# taptdoa_1_x.net
KiCad netlist of a schematic drawn in EAGLE
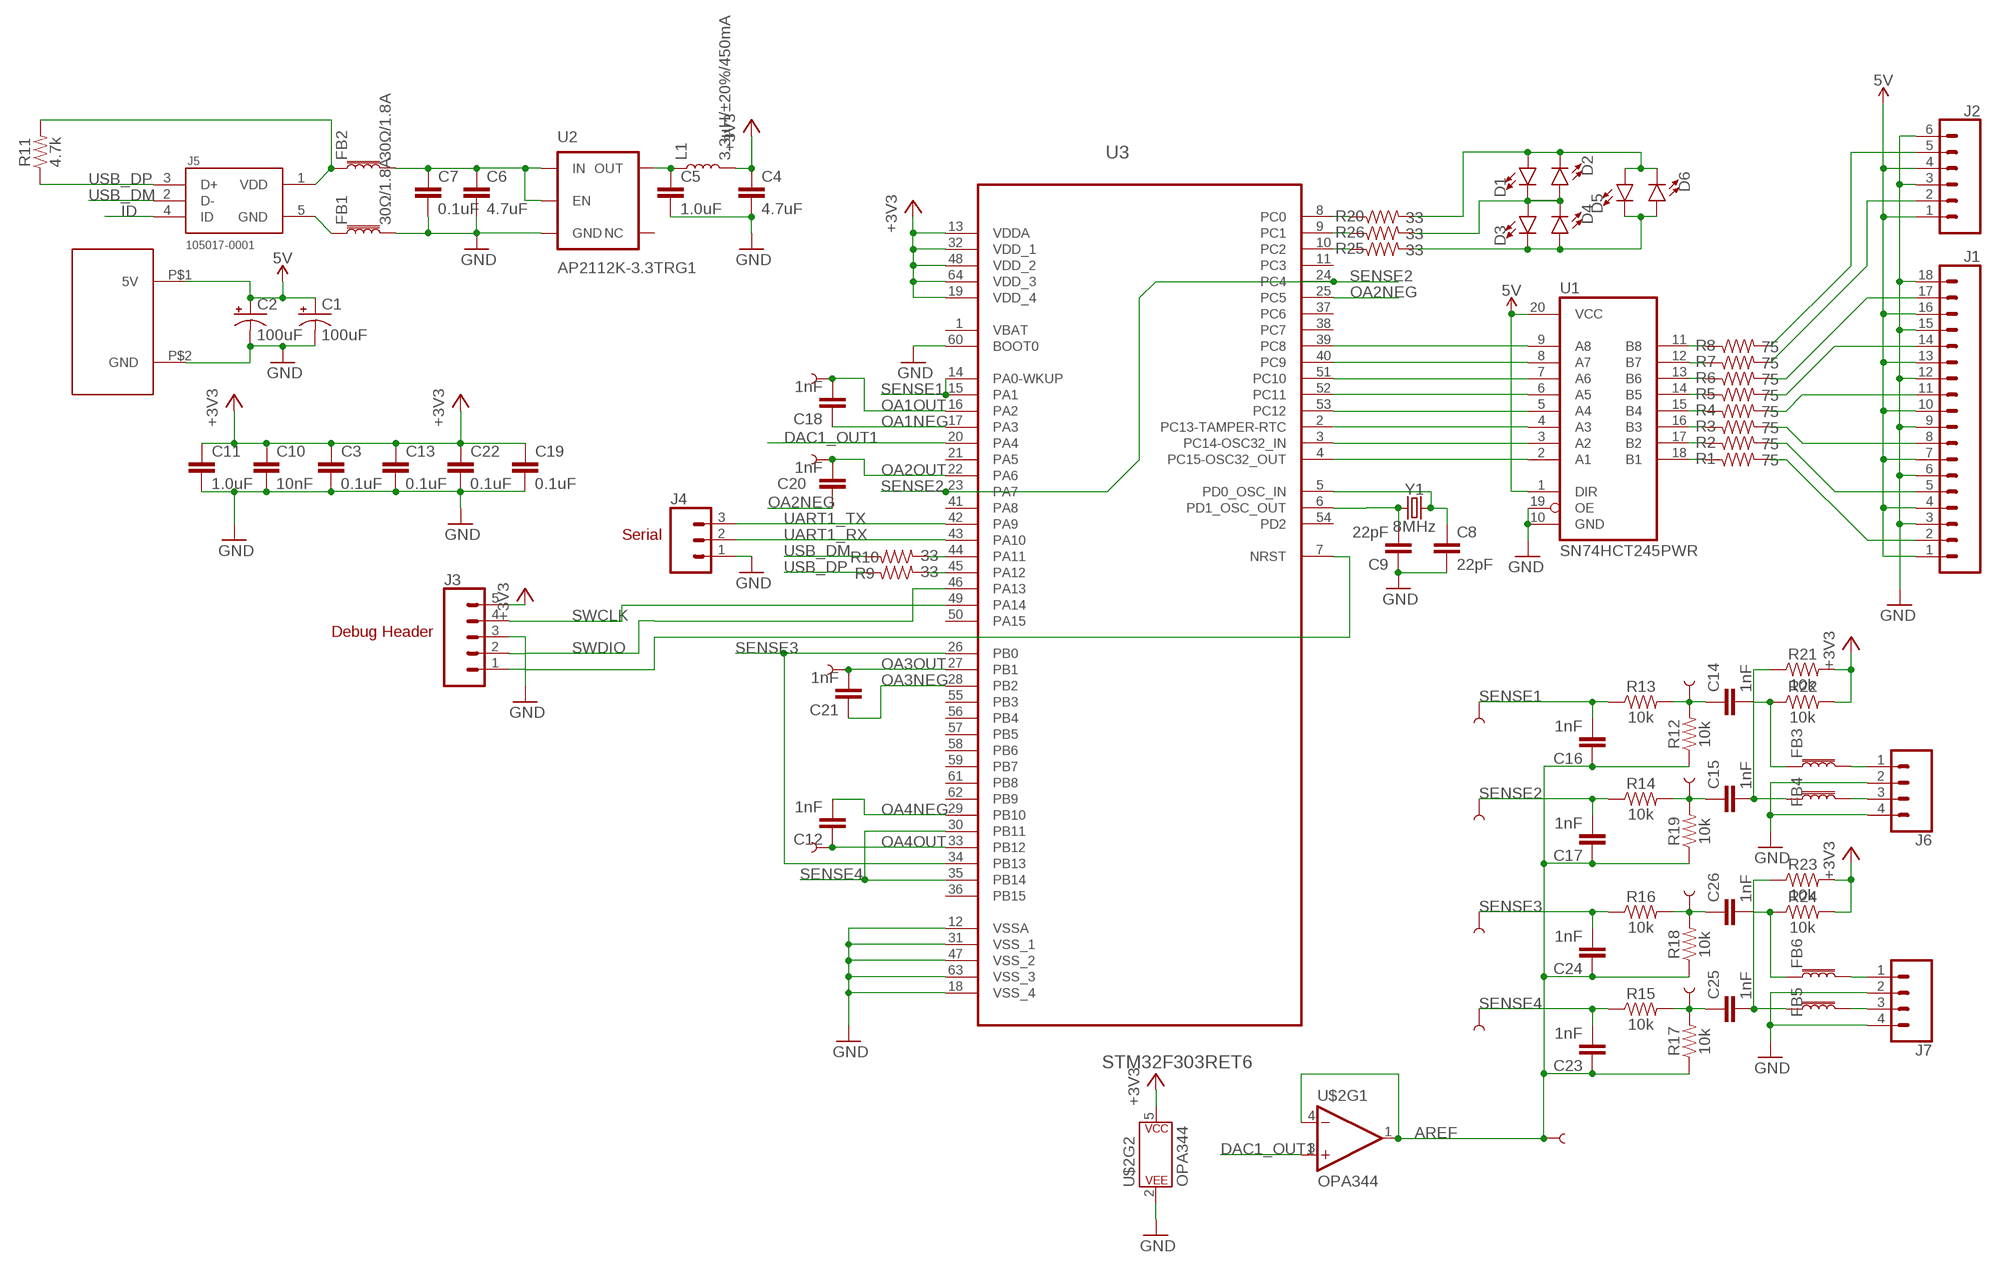
[diagram p0: schematic, sheet 1]

(export (version "E")
  (design (tool "Eeschema 10.0.6"))
  (components
    (comp (ref "C1")
      (value "100uF")
      (footprint "eagle-import:PANASONIC_D")
      (libsource (lib "eagle-import") (part "100UF-POLAR-25V-20%(ELEC)"))
    )
    (comp (ref "C2")
      (value "100uF")
      (footprint "eagle-import:PANASONIC_D")
      (libsource (lib "eagle-import") (part "100UF-POLAR-25V-20%(ELEC)"))
    )
    (comp (ref "C3")
      (value "0.1uF")
      (footprint "eagle-import:0603")
      (libsource (lib "eagle-import") (part "0.1UF-0603-25V-5%"))
    )
    (comp (ref "C4")
      (value "4.7uF")
      (footprint "eagle-import:0603")
      (libsource (lib "eagle-import") (part "4.7UF0603"))
    )
    (comp (ref "C5")
      (value "1.0uF")
      (footprint "eagle-import:0603")
      (libsource (lib "eagle-import") (part "1.0UF-0603-16V-10%"))
    )
    (comp (ref "C6")
      (value "4.7uF")
      (footprint "eagle-import:0603")
      (libsource (lib "eagle-import") (part "1.0UF-0603-16V-10%"))
    )
    (comp (ref "C7")
      (value "0.1uF")
      (footprint "eagle-import:0603")
      (libsource (lib "eagle-import") (part "0.1UF-0603-25V-5%"))
    )
    (comp (ref "C8")
      (value "22pF")
      (footprint "eagle-import:0603")
      (libsource (lib "eagle-import") (part "22PF-0603-50V-5%"))
    )
    (comp (ref "C9")
      (value "22pF")
      (footprint "eagle-import:0603")
      (libsource (lib "eagle-import") (part "22PF-0603-50V-5%"))
    )
    (comp (ref "C10")
      (value "10nF")
      (footprint "eagle-import:0603")
      (libsource (lib "eagle-import") (part "10NF-0603-50V-10%"))
    )
    (comp (ref "C11")
      (value "1.0uF")
      (footprint "eagle-import:0603")
      (libsource (lib "eagle-import") (part "1.0UF-0603-16V-10%"))
    )
    (comp (ref "C12")
      (value "1nF")
      (footprint "eagle-import:0603")
      (libsource (lib "eagle-import") (part "1.0UF-0603-16V-10%"))
    )
    (comp (ref "C13")
      (value "0.1uF")
      (footprint "eagle-import:0603")
      (libsource (lib "eagle-import") (part "0.1UF-0603-25V-5%"))
    )
    (comp (ref "C14")
      (value "1nF")
      (footprint "eagle-import:0603")
      (libsource (lib "eagle-import") (part "1.0UF-0603-16V-10%"))
    )
    (comp (ref "C15")
      (value "1nF")
      (footprint "eagle-import:0603")
      (libsource (lib "eagle-import") (part "1.0UF-0603-16V-10%"))
    )
    (comp (ref "C16")
      (value "1nF")
      (footprint "eagle-import:0603")
      (libsource (lib "eagle-import") (part "1.0UF-0603-16V-10%"))
    )
    (comp (ref "C17")
      (value "1nF")
      (footprint "eagle-import:0603")
      (libsource (lib "eagle-import") (part "1.0UF-0603-16V-10%"))
    )
    (comp (ref "C18")
      (value "1nF")
      (footprint "eagle-import:0603")
      (libsource (lib "eagle-import") (part "1.0UF-0603-16V-10%"))
    )
    (comp (ref "C19")
      (value "0.1uF")
      (footprint "eagle-import:0603")
      (libsource (lib "eagle-import") (part "0.1UF-0603-25V-5%"))
    )
    (comp (ref "C20")
      (value "1nF")
      (footprint "eagle-import:0603")
      (libsource (lib "eagle-import") (part "1.0UF-0603-16V-10%"))
    )
    (comp (ref "C21")
      (value "1nF")
      (footprint "eagle-import:0603")
      (libsource (lib "eagle-import") (part "1.0UF-0603-16V-10%"))
    )
    (comp (ref "C22")
      (value "0.1uF")
      (footprint "eagle-import:0603")
      (libsource (lib "eagle-import") (part "0.1UF-0603-25V-5%"))
    )
    (comp (ref "C23")
      (value "1nF")
      (footprint "eagle-import:0603")
      (libsource (lib "eagle-import") (part "1.0UF-0603-16V-10%"))
    )
    (comp (ref "C24")
      (value "1nF")
      (footprint "eagle-import:0603")
      (libsource (lib "eagle-import") (part "1.0UF-0603-16V-10%"))
    )
    (comp (ref "C25")
      (value "1nF")
      (footprint "eagle-import:0603")
      (libsource (lib "eagle-import") (part "1.0UF-0603-16V-10%"))
    )
    (comp (ref "C26")
      (value "1nF")
      (footprint "eagle-import:0603")
      (libsource (lib "eagle-import") (part "1.0UF-0603-16V-10%"))
    )
    (comp (ref "D1")
      (value "LED0603")
      (footprint "eagle-import:LED-0603")
      (libsource (lib "eagle-import") (part "LED0603"))
    )
    (comp (ref "D2")
      (value "LED0603")
      (footprint "eagle-import:LED-0603")
      (libsource (lib "eagle-import") (part "LED0603"))
    )
    (comp (ref "D3")
      (value "LED0603")
      (footprint "eagle-import:LED-0603")
      (libsource (lib "eagle-import") (part "LED0603"))
    )
    (comp (ref "D4")
      (value "LED0603")
      (footprint "eagle-import:LED-0603")
      (libsource (lib "eagle-import") (part "LED0603"))
    )
    (comp (ref "D5")
      (value "LED0603")
      (footprint "eagle-import:LED-0603")
      (libsource (lib "eagle-import") (part "LED0603"))
    )
    (comp (ref "D6")
      (value "LED0603")
      (footprint "eagle-import:LED-0603")
      (libsource (lib "eagle-import") (part "LED0603"))
    )
    (comp (ref "FB1")
      (value "30Ω/1.8A")
      (footprint "eagle-import:0603")
      (libsource (lib "eagle-import") (part "FERRITE_BEAD-0603"))
    )
    (comp (ref "FB2")
      (value "30Ω/1.8A")
      (footprint "eagle-import:0603")
      (libsource (lib "eagle-import") (part "FERRITE_BEAD-0603"))
    )
    (comp (ref "FB3")
      (value "30Ω/1.8A")
      (footprint "eagle-import:0603")
      (libsource (lib "eagle-import") (part "FERRITE_BEAD-0603"))
    )
    (comp (ref "FB4")
      (value "30Ω/1.8A")
      (footprint "eagle-import:0603")
      (libsource (lib "eagle-import") (part "FERRITE_BEAD-0603"))
    )
    (comp (ref "FB5")
      (value "30Ω/1.8A")
      (footprint "eagle-import:0603")
      (libsource (lib "eagle-import") (part "FERRITE_BEAD-0603"))
    )
    (comp (ref "FB6")
      (value "30Ω/1.8A")
      (footprint "eagle-import:0603")
      (libsource (lib "eagle-import") (part "FERRITE_BEAD-0603"))
    )
    (comp (ref "J1")
      (value "CONN_18")
      (footprint "eagle-import:1X18")
      (libsource (lib "eagle-import") (part "CONN_18"))
    )
    (comp (ref "J2")
      (value "CONN_06LOCK")
      (footprint "eagle-import:1X06_LOCK")
      (libsource (lib "eagle-import") (part "CONN_06LOCK"))
    )
    (comp (ref "J3")
      (value "CONN_05LOCK")
      (footprint "eagle-import:1X05_LOCK")
      (libsource (lib "eagle-import") (part "CONN_05LOCK"))
    )
    (comp (ref "J4")
      (value "CONN_03")
      (footprint "eagle-import:1X03")
      (libsource (lib "eagle-import") (part "CONN_03"))
    )
    (comp (ref "J5")
      (value "105017-0001")
      (footprint "eagle-import:MOLEX_105017-0001")
      (fields (field (name "MF") "Molex"))
      (libsource (lib "eagle-import") (part "105017-0001"))
    )
    (comp (ref "J6")
      (value "CONN_04LOCK_LONGPADS")
      (footprint "eagle-import:1X04_LOCK_LONGPADS")
      (libsource (lib "eagle-import") (part "CONN_04LOCK_LONGPADS"))
    )
    (comp (ref "J7")
      (value "CONN_04LOCK_LONGPADS")
      (footprint "eagle-import:1X04_LOCK_LONGPADS")
      (libsource (lib "eagle-import") (part "CONN_04LOCK_LONGPADS"))
    )
    (comp (ref "L1")
      (value "3.3µH/±20%/450mA")
      (footprint "eagle-import:0805")
      (libsource (lib "eagle-import") (part "INDUCTOR-0805-3.3UH"))
    )
    (comp (ref "R1")
      (value "75")
      (footprint "eagle-import:0603")
      (libsource (lib "eagle-import") (part "100OHM-0603-1/4W-5%"))
    )
    (comp (ref "R2")
      (value "75")
      (footprint "eagle-import:0603")
      (libsource (lib "eagle-import") (part "100OHM-0603-1/4W-5%"))
    )
    (comp (ref "R3")
      (value "75")
      (footprint "eagle-import:0603")
      (libsource (lib "eagle-import") (part "100OHM-0603-1/4W-5%"))
    )
    (comp (ref "R4")
      (value "75")
      (footprint "eagle-import:0603")
      (libsource (lib "eagle-import") (part "100OHM-0603-1/4W-5%"))
    )
    (comp (ref "R5")
      (value "75")
      (footprint "eagle-import:0603")
      (libsource (lib "eagle-import") (part "100OHM-0603-1/4W-5%"))
    )
    (comp (ref "R6")
      (value "75")
      (footprint "eagle-import:0603")
      (libsource (lib "eagle-import") (part "100OHM-0603-1/4W-5%"))
    )
    (comp (ref "R7")
      (value "75")
      (footprint "eagle-import:0603")
      (libsource (lib "eagle-import") (part "100OHM-0603-1/4W-5%"))
    )
    (comp (ref "R8")
      (value "75")
      (footprint "eagle-import:0603")
      (libsource (lib "eagle-import") (part "100OHM-0603-1/4W-5%"))
    )
    (comp (ref "R9")
      (value "33")
      (footprint "eagle-import:0603")
      (libsource (lib "eagle-import") (part "100OHM-0603-1/4W-5%"))
    )
    (comp (ref "R10")
      (value "33")
      (footprint "eagle-import:0603")
      (libsource (lib "eagle-import") (part "100OHM-0603-1/4W-5%"))
    )
    (comp (ref "R11")
      (value "4.7k")
      (footprint "eagle-import:0603")
      (libsource (lib "eagle-import") (part "RESISTOR0603"))
    )
    (comp (ref "R12")
      (value "10k")
      (footprint "eagle-import:0603")
      (libsource (lib "eagle-import") (part "RESISTOR0603"))
    )
    (comp (ref "R13")
      (value "10k")
      (footprint "eagle-import:0603")
      (libsource (lib "eagle-import") (part "RESISTOR0603"))
    )
    (comp (ref "R14")
      (value "10k")
      (footprint "eagle-import:0603")
      (libsource (lib "eagle-import") (part "RESISTOR0603"))
    )
    (comp (ref "R15")
      (value "10k")
      (footprint "eagle-import:0603")
      (libsource (lib "eagle-import") (part "RESISTOR0603"))
    )
    (comp (ref "R16")
      (value "10k")
      (footprint "eagle-import:0603")
      (libsource (lib "eagle-import") (part "RESISTOR0603"))
    )
    (comp (ref "R17")
      (value "10k")
      (footprint "eagle-import:0603")
      (libsource (lib "eagle-import") (part "RESISTOR0603"))
    )
    (comp (ref "R18")
      (value "10k")
      (footprint "eagle-import:0603")
      (libsource (lib "eagle-import") (part "RESISTOR0603"))
    )
    (comp (ref "R19")
      (value "10k")
      (footprint "eagle-import:0603")
      (libsource (lib "eagle-import") (part "RESISTOR0603"))
    )
    (comp (ref "R20")
      (value "33")
      (footprint "eagle-import:0603")
      (libsource (lib "eagle-import") (part "100OHM-0603-1/4W-5%"))
    )
    (comp (ref "R21")
      (value "10k")
      (footprint "eagle-import:0603")
      (libsource (lib "eagle-import") (part "RESISTOR0603"))
    )
    (comp (ref "R22")
      (value "10k")
      (footprint "eagle-import:0603")
      (libsource (lib "eagle-import") (part "RESISTOR0603"))
    )
    (comp (ref "R23")
      (value "10k")
      (footprint "eagle-import:0603")
      (libsource (lib "eagle-import") (part "RESISTOR0603"))
    )
    (comp (ref "R24")
      (value "10k")
      (footprint "eagle-import:0603")
      (libsource (lib "eagle-import") (part "RESISTOR0603"))
    )
    (comp (ref "R25")
      (value "33")
      (footprint "eagle-import:0603")
      (libsource (lib "eagle-import") (part "100OHM-0603-1/4W-5%"))
    )
    (comp (ref "R26")
      (value "33")
      (footprint "eagle-import:0603")
      (libsource (lib "eagle-import") (part "100OHM-0603-1/4W-5%"))
    )
    (comp (ref "TP1")
      (value "TEST-POINT3X4")
      (footprint "eagle-import:PAD.03X.04")
      (libsource (lib "eagle-import") (part "TEST-POINT3X4"))
    )
    (comp (ref "TP2")
      (value "TEST-POINT3X4")
      (footprint "eagle-import:PAD.03X.04")
      (libsource (lib "eagle-import") (part "TEST-POINT3X4"))
    )
    (comp (ref "TP3")
      (value "TEST-POINT3X4")
      (footprint "eagle-import:PAD.03X.04")
      (libsource (lib "eagle-import") (part "TEST-POINT3X4"))
    )
    (comp (ref "TP4")
      (value "TEST-POINT3X4")
      (footprint "eagle-import:PAD.03X.04")
      (libsource (lib "eagle-import") (part "TEST-POINT3X4"))
    )
    (comp (ref "TP5")
      (value "TEST-POINT3X4")
      (footprint "eagle-import:PAD.03X.04")
      (libsource (lib "eagle-import") (part "TEST-POINT3X4"))
    )
    (comp (ref "TP6")
      (value "TEST-POINT3X4")
      (footprint "eagle-import:PAD.03X.04")
      (libsource (lib "eagle-import") (part "TEST-POINT3X4"))
    )
    (comp (ref "TP7")
      (value "TEST-POINT3X4")
      (footprint "eagle-import:PAD.03X.04")
      (libsource (lib "eagle-import") (part "TEST-POINT3X4"))
    )
    (comp (ref "TP8")
      (value "TEST-POINT3X4")
      (footprint "eagle-import:PAD.03X.04")
      (libsource (lib "eagle-import") (part "TEST-POINT3X4"))
    )
    (comp (ref "TP9")
      (value "TEST-POINT3X4")
      (footprint "eagle-import:PAD.03X.04")
      (libsource (lib "eagle-import") (part "TEST-POINT3X4"))
    )
    (comp (ref "TP10")
      (value "TEST-POINT3X4")
      (footprint "eagle-import:PAD.03X.04")
      (libsource (lib "eagle-import") (part "TEST-POINT3X4"))
    )
    (comp (ref "TP11")
      (value "TEST-POINT3X4")
      (footprint "eagle-import:PAD.03X.04")
      (libsource (lib "eagle-import") (part "TEST-POINT3X4"))
    )
    (comp (ref "TP12")
      (value "TEST-POINT3X4")
      (footprint "eagle-import:PAD.03X.04")
      (libsource (lib "eagle-import") (part "TEST-POINT3X4"))
    )
    (comp (ref "TP13")
      (value "TEST-POINT3X4")
      (footprint "eagle-import:PAD.03X.04")
      (libsource (lib "eagle-import") (part "TEST-POINT3X4"))
    )
    (comp (ref "U$1")
      (value "XT30XT30_THRUHOLE")
      (footprint "eagle-import:ZT30")
      (libsource (lib "eagle-import") (part "XT30XT30_THRUHOLE"))
    )
    (comp (ref "U$2")
      (value "OPA344")
      (footprint "eagle-import:SOT23-5")
      (libsource (lib "eagle-import") (part "OPA344"))
    )
    (comp (ref "U1")
      (value "SN74HCT245PWR")
      (footprint "eagle-import:TSSOP20")
      (libsource (lib "eagle-import") (part "74245PW"))
    )
    (comp (ref "U2")
      (value "AP2112K-3.3TRG1")
      (footprint "eagle-import:SOT23-5")
      (libsource (lib "eagle-import") (part "V_REG_AP2112K-3.3V"))
    )
    (comp (ref "U3")
      (value "STM32F303RET6")
      (footprint "eagle-import:QFP50P1200X1200X160-64N")
      (fields (field (name "MPN") "STM32F103RBT6"))
      (libsource (lib "eagle-import") (part "STM32F103RBT6"))
    )
    (comp (ref "Y1")
      (value "8MHz")
      (footprint "eagle-import:HC49UP")
      (libsource (lib "eagle-import") (part "CRYSTALSMD-HC49UP"))
    )
  )
  (nets
    (net (code "1") (name "+3V3") (class "Default")
      (node (ref "C10") (pin "1") (pinfunction "1_1") (pintype "passive"))
      (node (ref "C11") (pin "1") (pinfunction "1_1") (pintype "passive"))
      (node (ref "C13") (pin "1") (pinfunction "1_1") (pintype "passive"))
      (node (ref "C19") (pin "1") (pinfunction "1_1") (pintype "passive"))
      (node (ref "C22") (pin "1") (pinfunction "1_1") (pintype "passive"))
      (node (ref "C3") (pin "1") (pinfunction "1_1") (pintype "passive"))
      (node (ref "C4") (pin "1") (pinfunction "1_1") (pintype "passive"))
      (node (ref "J3") (pin "5") (pinfunction "5_5") (pintype "passive"))
      (node (ref "L1") (pin "2") (pinfunction "2_2") (pintype "passive"))
      (node (ref "R21") (pin "2") (pinfunction "2_2") (pintype "passive"))
      (node (ref "R22") (pin "2") (pinfunction "2_2") (pintype "passive"))
      (node (ref "R23") (pin "2") (pinfunction "2_2") (pintype "passive"))
      (node (ref "R24") (pin "2") (pinfunction "2_2") (pintype "passive"))
      (node (ref "U$2") (pin "5") (pinfunction "P$V+_5") (pintype "bidirectional"))
      (node (ref "U3") (pin "13") (pinfunction "VDDA_13") (pintype "power_in"))
      (node (ref "U3") (pin "19") (pinfunction "VDD_4_19") (pintype "power_in"))
      (node (ref "U3") (pin "32") (pinfunction "VDD_1_32") (pintype "power_in"))
      (node (ref "U3") (pin "48") (pinfunction "VDD_2_48") (pintype "power_in"))
      (node (ref "U3") (pin "64") (pinfunction "VDD_3_64") (pintype "power_in"))
    )
    (net (code "2") (name "/AREF") (class "Default")
      (node (ref "C16") (pin "1") (pinfunction "1_1") (pintype "passive"))
      (node (ref "C17") (pin "1") (pinfunction "1_1") (pintype "passive"))
      (node (ref "C23") (pin "1") (pinfunction "1_1") (pintype "passive"))
      (node (ref "C24") (pin "1") (pinfunction "1_1") (pintype "passive"))
      (node (ref "R12") (pin "1") (pinfunction "1_1") (pintype "passive"))
      (node (ref "R17") (pin "1") (pinfunction "1_1") (pintype "passive"))
      (node (ref "R18") (pin "1") (pinfunction "1_1") (pintype "passive"))
      (node (ref "R19") (pin "1") (pinfunction "1_1") (pintype "passive"))
      (node (ref "TP8") (pin "P$1") (pinfunction "1_P$1") (pintype "bidirectional"))
      (node (ref "U$2") (pin "1") (pinfunction "OUT_1") (pintype "output"))
      (node (ref "U$2") (pin "4") (pinfunction "-IN_4") (pintype "input"))
    )
    (net (code "3") (name "/DAC1_OUT1") (class "Default")
      (node (ref "U$2") (pin "3") (pinfunction "+IN_3") (pintype "input"))
      (node (ref "U3") (pin "20") (pinfunction "PA4_20") (pintype "bidirectional"))
    )
    (net (code "4") (name "/ID") (class "Default")
      (node (ref "J5") (pin "4") (pinfunction "ID_4") (pintype "passive"))
    )
    (net (code "5") (name "/OA1NEG") (class "Default")
      (node (ref "C18") (pin "1") (pinfunction "1_1") (pintype "passive"))
      (node (ref "U3") (pin "17") (pinfunction "PA3_17") (pintype "bidirectional"))
    )
    (net (code "6") (name "/OA1OUT") (class "Default")
      (node (ref "C18") (pin "2") (pinfunction "2_2") (pintype "passive"))
      (node (ref "TP6") (pin "P$1") (pinfunction "1_P$1") (pintype "bidirectional"))
      (node (ref "U3") (pin "16") (pinfunction "PA2_16") (pintype "bidirectional"))
    )
    (net (code "7") (name "/OA2NEG") (class "Default")
      (node (ref "C20") (pin "1") (pinfunction "1_1") (pintype "passive"))
      (node (ref "U3") (pin "25") (pinfunction "PC5_25") (pintype "bidirectional"))
    )
    (net (code "8") (name "/OA2OUT") (class "Default")
      (node (ref "C20") (pin "2") (pinfunction "2_2") (pintype "passive"))
      (node (ref "TP7") (pin "P$1") (pinfunction "1_P$1") (pintype "bidirectional"))
      (node (ref "U3") (pin "22") (pinfunction "PA6_22") (pintype "bidirectional"))
    )
    (net (code "9") (name "/OA3NEG") (class "Default")
      (node (ref "C21") (pin "1") (pinfunction "1_1") (pintype "passive"))
      (node (ref "U3") (pin "28") (pinfunction "PB2_28") (pintype "bidirectional"))
    )
    (net (code "10") (name "/OA3OUT") (class "Default")
      (node (ref "C21") (pin "2") (pinfunction "2_2") (pintype "passive"))
      (node (ref "TP9") (pin "P$1") (pinfunction "1_P$1") (pintype "bidirectional"))
      (node (ref "U3") (pin "27") (pinfunction "PB1_27") (pintype "bidirectional"))
    )
    (net (code "11") (name "/OA4NEG") (class "Default")
      (node (ref "C12") (pin "2") (pinfunction "2_2") (pintype "passive"))
      (node (ref "U3") (pin "29") (pinfunction "PB10_29") (pintype "bidirectional"))
    )
    (net (code "12") (name "/OA4OUT") (class "Default")
      (node (ref "C12") (pin "1") (pinfunction "1_1") (pintype "passive"))
      (node (ref "TP1") (pin "P$1") (pinfunction "1_P$1") (pintype "bidirectional"))
      (node (ref "U3") (pin "33") (pinfunction "PB12_33") (pintype "bidirectional"))
    )
    (net (code "13") (name "/SENSE1") (class "Default")
      (node (ref "C16") (pin "2") (pinfunction "2_2") (pintype "passive"))
      (node (ref "R13") (pin "1") (pinfunction "1_1") (pintype "passive"))
      (node (ref "TP4") (pin "P$1") (pinfunction "1_P$1") (pintype "bidirectional"))
      (node (ref "U3") (pin "14") (pinfunction "PA0-WKUP_14") (pintype "bidirectional"))
      (node (ref "U3") (pin "15") (pinfunction "PA1_15") (pintype "bidirectional"))
    )
    (net (code "14") (name "/SENSE2") (class "Default")
      (node (ref "C17") (pin "2") (pinfunction "2_2") (pintype "passive"))
      (node (ref "R14") (pin "1") (pinfunction "1_1") (pintype "passive"))
      (node (ref "TP5") (pin "P$1") (pinfunction "1_P$1") (pintype "bidirectional"))
      (node (ref "U3") (pin "23") (pinfunction "PA7_23") (pintype "bidirectional"))
      (node (ref "U3") (pin "24") (pinfunction "PC4_24") (pintype "bidirectional"))
    )
    (net (code "15") (name "/SENSE3") (class "Default")
      (node (ref "C24") (pin "2") (pinfunction "2_2") (pintype "passive"))
      (node (ref "R16") (pin "1") (pinfunction "1_1") (pintype "passive"))
      (node (ref "TP10") (pin "P$1") (pinfunction "1_P$1") (pintype "bidirectional"))
      (node (ref "U3") (pin "26") (pinfunction "PB0_26") (pintype "bidirectional"))
      (node (ref "U3") (pin "34") (pinfunction "PB13_34") (pintype "bidirectional"))
    )
    (net (code "16") (name "/SENSE4") (class "Default")
      (node (ref "C23") (pin "2") (pinfunction "2_2") (pintype "passive"))
      (node (ref "R15") (pin "1") (pinfunction "1_1") (pintype "passive"))
      (node (ref "TP11") (pin "P$1") (pinfunction "1_P$1") (pintype "bidirectional"))
      (node (ref "U3") (pin "30") (pinfunction "PB11_30") (pintype "bidirectional"))
      (node (ref "U3") (pin "35") (pinfunction "PB14_35") (pintype "bidirectional"))
    )
    (net (code "17") (name "/UART1_RX") (class "Default")
      (node (ref "J4") (pin "2") (pinfunction "2_2") (pintype "passive"))
      (node (ref "U3") (pin "43") (pinfunction "PA10_43") (pintype "bidirectional"))
    )
    (net (code "18") (name "/UART1_TX") (class "Default")
      (node (ref "J4") (pin "3") (pinfunction "3_3") (pintype "passive"))
      (node (ref "U3") (pin "42") (pinfunction "PA9_42") (pintype "bidirectional"))
    )
    (net (code "19") (name "/USB_DM") (class "Default")
      (node (ref "J5") (pin "2") (pinfunction "D-_2") (pintype "bidirectional"))
      (node (ref "R10") (pin "2") (pinfunction "2_2") (pintype "passive"))
    )
    (net (code "20") (name "/USB_DP") (class "Default")
      (node (ref "J5") (pin "3") (pinfunction "D+_3") (pintype "bidirectional"))
      (node (ref "R11") (pin "1") (pinfunction "1_1") (pintype "passive"))
      (node (ref "R9") (pin "2") (pinfunction "2_2") (pintype "passive"))
    )
    (net (code "21") (name "5V") (class "Default")
      (node (ref "C1") (pin "+") (pinfunction "+_+") (pintype "passive"))
      (node (ref "C2") (pin "+") (pinfunction "+_+") (pintype "passive"))
      (node (ref "J1") (pin "1") (pinfunction "1_1") (pintype "passive"))
      (node (ref "J1") (pin "10") (pinfunction "10_10") (pintype "passive"))
      (node (ref "J1") (pin "13") (pinfunction "13_13") (pintype "passive"))
      (node (ref "J1") (pin "16") (pinfunction "16_16") (pintype "passive"))
      (node (ref "J1") (pin "4") (pinfunction "4_4") (pintype "passive"))
      (node (ref "J1") (pin "7") (pinfunction "7_7") (pintype "passive"))
      (node (ref "J2") (pin "1") (pinfunction "1_1") (pintype "passive"))
      (node (ref "J2") (pin "4") (pinfunction "4_4") (pintype "passive"))
      (node (ref "U$1") (pin "P$1") (pinfunction "5V_P$1") (pintype "bidirectional"))
      (node (ref "U1") (pin "1") (pinfunction "DIR_1") (pintype "input"))
      (node (ref "U1") (pin "20") (pinfunction "VCC_20") (pintype "bidirectional"))
    )
    (net (code "22") (name "GND") (class "Default")
      (node (ref "C1") (pin "-") (pinfunction "-_-") (pintype "passive"))
      (node (ref "C10") (pin "2") (pinfunction "2_2") (pintype "passive"))
      (node (ref "C11") (pin "2") (pinfunction "2_2") (pintype "passive"))
      (node (ref "C13") (pin "2") (pinfunction "2_2") (pintype "passive"))
      (node (ref "C19") (pin "2") (pinfunction "2_2") (pintype "passive"))
      (node (ref "C2") (pin "-") (pinfunction "-_-") (pintype "passive"))
      (node (ref "C22") (pin "2") (pinfunction "2_2") (pintype "passive"))
      (node (ref "C3") (pin "2") (pinfunction "2_2") (pintype "passive"))
      (node (ref "C4") (pin "2") (pinfunction "2_2") (pintype "passive"))
      (node (ref "C5") (pin "2") (pinfunction "2_2") (pintype "passive"))
      (node (ref "C6") (pin "2") (pinfunction "2_2") (pintype "passive"))
      (node (ref "C7") (pin "2") (pinfunction "2_2") (pintype "passive"))
      (node (ref "C8") (pin "2") (pinfunction "2_2") (pintype "passive"))
      (node (ref "C9") (pin "1") (pinfunction "1_1") (pintype "passive"))
      (node (ref "FB1") (pin "2") (pinfunction "2_2") (pintype "passive"))
      (node (ref "J1") (pin "12") (pinfunction "12_12") (pintype "passive"))
      (node (ref "J1") (pin "15") (pinfunction "15_15") (pintype "passive"))
      (node (ref "J1") (pin "18") (pinfunction "18_18") (pintype "passive"))
      (node (ref "J1") (pin "3") (pinfunction "3_3") (pintype "passive"))
      (node (ref "J1") (pin "6") (pinfunction "6_6") (pintype "passive"))
      (node (ref "J1") (pin "9") (pinfunction "9_9") (pintype "passive"))
      (node (ref "J2") (pin "3") (pinfunction "3_3") (pintype "passive"))
      (node (ref "J2") (pin "6") (pinfunction "6_6") (pintype "passive"))
      (node (ref "J3") (pin "3") (pinfunction "3_3") (pintype "passive"))
      (node (ref "J4") (pin "1") (pinfunction "1_1") (pintype "passive"))
      (node (ref "J6") (pin "2") (pinfunction "2_2") (pintype "passive"))
      (node (ref "J6") (pin "4") (pinfunction "4_4") (pintype "passive"))
      (node (ref "J7") (pin "2") (pinfunction "2_2") (pintype "passive"))
      (node (ref "J7") (pin "4") (pinfunction "4_4") (pintype "passive"))
      (node (ref "U$1") (pin "P$2") (pinfunction "GND_P$2") (pintype "bidirectional"))
      (node (ref "U$2") (pin "2") (pinfunction "P$V-_2") (pintype "bidirectional"))
      (node (ref "U1") (pin "10") (pinfunction "GND_10") (pintype "bidirectional"))
      (node (ref "U1") (pin "19") (pinfunction "OE_19") (pintype "input"))
      (node (ref "U2") (pin "2") (pinfunction "GND_2") (pintype "input"))
      (node (ref "U3") (pin "12") (pinfunction "VSSA_12") (pintype "passive"))
      (node (ref "U3") (pin "18") (pinfunction "VSS_4_18") (pintype "passive"))
      (node (ref "U3") (pin "31") (pinfunction "VSS_1_31") (pintype "passive"))
      (node (ref "U3") (pin "47") (pinfunction "VSS_2_47") (pintype "passive"))
      (node (ref "U3") (pin "60") (pinfunction "BOOT0_60") (pintype "input"))
      (node (ref "U3") (pin "63") (pinfunction "VSS_3_63") (pintype "passive"))
    )
    (net (code "23") (name "Net-(C14-Pad2)") (class "Default")
      (node (ref "C14") (pin "2") (pinfunction "2_2") (pintype "passive"))
      (node (ref "FB3") (pin "1") (pinfunction "1_1") (pintype "passive"))
      (node (ref "R22") (pin "1") (pinfunction "1_1") (pintype "passive"))
    )
    (net (code "24") (name "Net-(C15-Pad2)") (class "Default")
      (node (ref "C15") (pin "2") (pinfunction "2_2") (pintype "passive"))
      (node (ref "FB4") (pin "1") (pinfunction "1_1") (pintype "passive"))
      (node (ref "R21") (pin "1") (pinfunction "1_1") (pintype "passive"))
    )
    (net (code "25") (name "Net-(C25-Pad2)") (class "Default")
      (node (ref "C25") (pin "2") (pinfunction "2_2") (pintype "passive"))
      (node (ref "FB5") (pin "1") (pinfunction "1_1") (pintype "passive"))
      (node (ref "R23") (pin "1") (pinfunction "1_1") (pintype "passive"))
    )
    (net (code "26") (name "Net-(C26-Pad2)") (class "Default")
      (node (ref "C26") (pin "2") (pinfunction "2_2") (pintype "passive"))
      (node (ref "FB6") (pin "1") (pinfunction "1_1") (pintype "passive"))
      (node (ref "R24") (pin "1") (pinfunction "1_1") (pintype "passive"))
    )
    (net (code "27") (name "Net-(D1-PadA)") (class "Default")
      (node (ref "D1") (pin "A") (pinfunction "A_A") (pintype "passive"))
      (node (ref "D2") (pin "C") (pinfunction "C_C") (pintype "passive"))
      (node (ref "D5") (pin "A") (pinfunction "A_A") (pintype "passive"))
      (node (ref "D6") (pin "C") (pinfunction "C_C") (pintype "passive"))
      (node (ref "R20") (pin "2") (pinfunction "2_2") (pintype "passive"))
    )
    (net (code "28") (name "Net-(D1-PadC)") (class "Default")
      (node (ref "D1") (pin "C") (pinfunction "C_C") (pintype "passive"))
      (node (ref "D2") (pin "A") (pinfunction "A_A") (pintype "passive"))
      (node (ref "D3") (pin "A") (pinfunction "A_A") (pintype "passive"))
      (node (ref "D4") (pin "C") (pinfunction "C_C") (pintype "passive"))
      (node (ref "R26") (pin "2") (pinfunction "2_2") (pintype "passive"))
    )
    (net (code "29") (name "Net-(D3-PadC)") (class "Default")
      (node (ref "D3") (pin "C") (pinfunction "C_C") (pintype "passive"))
      (node (ref "D4") (pin "A") (pinfunction "A_A") (pintype "passive"))
      (node (ref "D5") (pin "C") (pinfunction "C_C") (pintype "passive"))
      (node (ref "D6") (pin "A") (pinfunction "A_A") (pintype "passive"))
      (node (ref "R25") (pin "2") (pinfunction "2_2") (pintype "passive"))
    )
    (net (code "30") (name "Net-(FB3-Pad2)") (class "Default")
      (node (ref "FB3") (pin "2") (pinfunction "2_2") (pintype "passive"))
      (node (ref "J6") (pin "1") (pinfunction "1_1") (pintype "passive"))
    )
    (net (code "31") (name "Net-(FB4-Pad2)") (class "Default")
      (node (ref "FB4") (pin "2") (pinfunction "2_2") (pintype "passive"))
      (node (ref "J6") (pin "3") (pinfunction "3_3") (pintype "passive"))
    )
    (net (code "32") (name "Net-(FB5-Pad2)") (class "Default")
      (node (ref "FB5") (pin "2") (pinfunction "2_2") (pintype "passive"))
      (node (ref "J7") (pin "3") (pinfunction "3_3") (pintype "passive"))
    )
    (net (code "33") (name "Net-(FB6-Pad2)") (class "Default")
      (node (ref "FB6") (pin "2") (pinfunction "2_2") (pintype "passive"))
      (node (ref "J7") (pin "1") (pinfunction "1_1") (pintype "passive"))
    )
    (net (code "34") (name "Net-(J1-Pad2)") (class "Default")
      (node (ref "J1") (pin "2") (pinfunction "2_2") (pintype "passive"))
      (node (ref "R1") (pin "2") (pinfunction "2_2") (pintype "passive"))
    )
    (net (code "35") (name "Net-(J1-Pad5)") (class "Default")
      (node (ref "J1") (pin "5") (pinfunction "5_5") (pintype "passive"))
      (node (ref "R2") (pin "2") (pinfunction "2_2") (pintype "passive"))
    )
    (net (code "36") (name "Net-(J1-Pad8)") (class "Default")
      (node (ref "J1") (pin "8") (pinfunction "8_8") (pintype "passive"))
      (node (ref "R3") (pin "2") (pinfunction "2_2") (pintype "passive"))
    )
    (net (code "37") (name "Net-(J1-Pad11)") (class "Default")
      (node (ref "J1") (pin "11") (pinfunction "11_11") (pintype "passive"))
      (node (ref "R4") (pin "2") (pinfunction "2_2") (pintype "passive"))
    )
    (net (code "38") (name "Net-(J1-Pad14)") (class "Default")
      (node (ref "J1") (pin "14") (pinfunction "14_14") (pintype "passive"))
      (node (ref "R5") (pin "2") (pinfunction "2_2") (pintype "passive"))
    )
    (net (code "39") (name "Net-(J1-Pad17)") (class "Default")
      (node (ref "J1") (pin "17") (pinfunction "17_17") (pintype "passive"))
      (node (ref "R6") (pin "2") (pinfunction "2_2") (pintype "passive"))
    )
    (net (code "40") (name "Net-(J2-Pad2)") (class "Default")
      (node (ref "J2") (pin "2") (pinfunction "2_2") (pintype "passive"))
      (node (ref "R7") (pin "2") (pinfunction "2_2") (pintype "passive"))
    )
    (net (code "41") (name "Net-(J2-Pad5)") (class "Default")
      (node (ref "J2") (pin "5") (pinfunction "5_5") (pintype "passive"))
      (node (ref "R8") (pin "2") (pinfunction "2_2") (pintype "passive"))
    )
    (net (code "42") (name "Net-(J5-GND)") (class "Default")
      (node (ref "FB1") (pin "1") (pinfunction "1_1") (pintype "passive"))
      (node (ref "J5") (pin "5") (pinfunction "GND_5") (pintype "power_in"))
    )
    (net (code "43") (name "Net-(J5-VDD)") (class "Default")
      (node (ref "FB2") (pin "1") (pinfunction "1_1") (pintype "passive"))
      (node (ref "J5") (pin "1") (pinfunction "VDD_1") (pintype "power_in"))
      (node (ref "R11") (pin "2") (pinfunction "2_2") (pintype "passive"))
    )
    (net (code "44") (name "Net-(TP2-1)") (class "Default")
      (node (ref "C14") (pin "1") (pinfunction "1_1") (pintype "passive"))
      (node (ref "R12") (pin "2") (pinfunction "2_2") (pintype "passive"))
      (node (ref "R13") (pin "2") (pinfunction "2_2") (pintype "passive"))
      (node (ref "TP2") (pin "P$1") (pinfunction "1_P$1") (pintype "bidirectional"))
    )
    (net (code "45") (name "Net-(TP3-1)") (class "Default")
      (node (ref "C15") (pin "1") (pinfunction "1_1") (pintype "passive"))
      (node (ref "R14") (pin "2") (pinfunction "2_2") (pintype "passive"))
      (node (ref "R19") (pin "2") (pinfunction "2_2") (pintype "passive"))
      (node (ref "TP3") (pin "P$1") (pinfunction "1_P$1") (pintype "bidirectional"))
    )
    (net (code "46") (name "Net-(TP12-1)") (class "Default")
      (node (ref "C26") (pin "1") (pinfunction "1_1") (pintype "passive"))
      (node (ref "R16") (pin "2") (pinfunction "2_2") (pintype "passive"))
      (node (ref "R18") (pin "2") (pinfunction "2_2") (pintype "passive"))
      (node (ref "TP12") (pin "P$1") (pinfunction "1_P$1") (pintype "bidirectional"))
    )
    (net (code "47") (name "Net-(TP13-1)") (class "Default")
      (node (ref "C25") (pin "1") (pinfunction "1_1") (pintype "passive"))
      (node (ref "R15") (pin "2") (pinfunction "2_2") (pintype "passive"))
      (node (ref "R17") (pin "2") (pinfunction "2_2") (pintype "passive"))
      (node (ref "TP13") (pin "P$1") (pinfunction "1_P$1") (pintype "bidirectional"))
    )
    (net (code "48") (name "Net-(U1-A1)") (class "Default")
      (node (ref "U1") (pin "2") (pinfunction "A1_2") (pintype "bidirectional"))
      (node (ref "U3") (pin "4") (pinfunction "PC15-OSC32_OUT_4") (pintype "bidirectional"))
    )
    (net (code "49") (name "Net-(U1-A2)") (class "Default")
      (node (ref "U1") (pin "3") (pinfunction "A2_3") (pintype "bidirectional"))
      (node (ref "U3") (pin "3") (pinfunction "PC14-OSC32_IN_3") (pintype "bidirectional"))
    )
    (net (code "50") (name "Net-(U1-A3)") (class "Default")
      (node (ref "U1") (pin "4") (pinfunction "A3_4") (pintype "bidirectional"))
      (node (ref "U3") (pin "2") (pinfunction "PC13-TAMPER-RTC_2") (pintype "bidirectional"))
    )
    (net (code "51") (name "Net-(U1-A4)") (class "Default")
      (node (ref "U1") (pin "5") (pinfunction "A4_5") (pintype "bidirectional"))
      (node (ref "U3") (pin "53") (pinfunction "PC12_53") (pintype "bidirectional"))
    )
    (net (code "52") (name "Net-(U1-A5)") (class "Default")
      (node (ref "U1") (pin "6") (pinfunction "A5_6") (pintype "bidirectional"))
      (node (ref "U3") (pin "52") (pinfunction "PC11_52") (pintype "bidirectional"))
    )
    (net (code "53") (name "Net-(U1-A6)") (class "Default")
      (node (ref "U1") (pin "7") (pinfunction "A6_7") (pintype "bidirectional"))
      (node (ref "U3") (pin "51") (pinfunction "PC10_51") (pintype "bidirectional"))
    )
    (net (code "54") (name "Net-(U1-A7)") (class "Default")
      (node (ref "U1") (pin "8") (pinfunction "A7_8") (pintype "bidirectional"))
      (node (ref "U3") (pin "40") (pinfunction "PC9_40") (pintype "bidirectional"))
    )
    (net (code "55") (name "Net-(U1-A8)") (class "Default")
      (node (ref "U1") (pin "9") (pinfunction "A8_9") (pintype "bidirectional"))
      (node (ref "U3") (pin "39") (pinfunction "PC8_39") (pintype "bidirectional"))
    )
    (net (code "56") (name "Net-(U1-B1)") (class "Default")
      (node (ref "R1") (pin "1") (pinfunction "1_1") (pintype "passive"))
      (node (ref "U1") (pin "18") (pinfunction "B1_18") (pintype "bidirectional"))
    )
    (net (code "57") (name "Net-(U1-B2)") (class "Default")
      (node (ref "R2") (pin "1") (pinfunction "1_1") (pintype "passive"))
      (node (ref "U1") (pin "17") (pinfunction "B2_17") (pintype "bidirectional"))
    )
    (net (code "58") (name "Net-(U1-B3)") (class "Default")
      (node (ref "R3") (pin "1") (pinfunction "1_1") (pintype "passive"))
      (node (ref "U1") (pin "16") (pinfunction "B3_16") (pintype "bidirectional"))
    )
    (net (code "59") (name "Net-(U1-B4)") (class "Default")
      (node (ref "R4") (pin "1") (pinfunction "1_1") (pintype "passive"))
      (node (ref "U1") (pin "15") (pinfunction "B4_15") (pintype "bidirectional"))
    )
    (net (code "60") (name "Net-(U1-B5)") (class "Default")
      (node (ref "R5") (pin "1") (pinfunction "1_1") (pintype "passive"))
      (node (ref "U1") (pin "14") (pinfunction "B5_14") (pintype "bidirectional"))
    )
    (net (code "61") (name "Net-(U1-B6)") (class "Default")
      (node (ref "R6") (pin "1") (pinfunction "1_1") (pintype "passive"))
      (node (ref "U1") (pin "13") (pinfunction "B6_13") (pintype "bidirectional"))
    )
    (net (code "62") (name "Net-(U1-B7)") (class "Default")
      (node (ref "R7") (pin "1") (pinfunction "1_1") (pintype "passive"))
      (node (ref "U1") (pin "12") (pinfunction "B7_12") (pintype "bidirectional"))
    )
    (net (code "63") (name "Net-(U1-B8)") (class "Default")
      (node (ref "R8") (pin "1") (pinfunction "1_1") (pintype "passive"))
      (node (ref "U1") (pin "11") (pinfunction "B8_11") (pintype "bidirectional"))
    )
    (net (code "64") (name "Net-(U2-EN)") (class "Default")
      (node (ref "C6") (pin "1") (pinfunction "1_1") (pintype "passive"))
      (node (ref "C7") (pin "1") (pinfunction "1_1") (pintype "passive"))
      (node (ref "FB2") (pin "2") (pinfunction "2_2") (pintype "passive"))
      (node (ref "U2") (pin "1") (pinfunction "IN_1") (pintype "input"))
      (node (ref "U2") (pin "3") (pinfunction "EN_3") (pintype "input"))
    )
    (net (code "65") (name "Net-(U2-OUT)") (class "Default")
      (node (ref "C5") (pin "1") (pinfunction "1_1") (pintype "passive"))
      (node (ref "L1") (pin "1") (pinfunction "1_1") (pintype "passive"))
      (node (ref "U2") (pin "5") (pinfunction "OUT_5") (pintype "passive"))
    )
    (net (code "66") (name "Net-(U3-NRST)") (class "Default")
      (node (ref "J3") (pin "1") (pinfunction "1_1") (pintype "passive"))
      (node (ref "U3") (pin "7") (pinfunction "NRST_7") (pintype "bidirectional"))
    )
    (net (code "67") (name "Net-(U3-PA11)") (class "Default")
      (node (ref "R10") (pin "1") (pinfunction "1_1") (pintype "passive"))
      (node (ref "U3") (pin "44") (pinfunction "PA11_44") (pintype "bidirectional"))
    )
    (net (code "68") (name "Net-(U3-PA12)") (class "Default")
      (node (ref "R9") (pin "1") (pinfunction "1_1") (pintype "passive"))
      (node (ref "U3") (pin "45") (pinfunction "PA12_45") (pintype "bidirectional"))
    )
    (net (code "69") (name "Net-(U3-PA13)") (class "Default")
      (node (ref "J3") (pin "2") (pinfunction "2_2") (pintype "passive"))
      (node (ref "U3") (pin "46") (pinfunction "PA13_46") (pintype "bidirectional"))
    )
    (net (code "70") (name "Net-(U3-PA14)") (class "Default")
      (node (ref "J3") (pin "4") (pinfunction "4_4") (pintype "passive"))
      (node (ref "U3") (pin "49") (pinfunction "PA14_49") (pintype "bidirectional"))
    )
    (net (code "71") (name "Net-(U3-PC0)") (class "Default")
      (node (ref "R20") (pin "1") (pinfunction "1_1") (pintype "passive"))
      (node (ref "U3") (pin "8") (pinfunction "PC0_8") (pintype "bidirectional"))
    )
    (net (code "72") (name "Net-(U3-PC1)") (class "Default")
      (node (ref "R26") (pin "1") (pinfunction "1_1") (pintype "passive"))
      (node (ref "U3") (pin "9") (pinfunction "PC1_9") (pintype "bidirectional"))
    )
    (net (code "73") (name "Net-(U3-PC2)") (class "Default")
      (node (ref "R25") (pin "1") (pinfunction "1_1") (pintype "passive"))
      (node (ref "U3") (pin "10") (pinfunction "PC2_10") (pintype "bidirectional"))
    )
    (net (code "74") (name "Net-(U3-PD0_OSC_IN)") (class "Default")
      (node (ref "C8") (pin "1") (pinfunction "1_1") (pintype "passive"))
      (node (ref "U3") (pin "5") (pinfunction "PD0_OSC_IN_5") (pintype "bidirectional"))
      (node (ref "Y1") (pin "2") (pinfunction "2_2") (pintype "passive"))
    )
    (net (code "75") (name "Net-(U3-PD1_OSC_OUT)") (class "Default")
      (node (ref "C9") (pin "2") (pinfunction "2_2") (pintype "passive"))
      (node (ref "U3") (pin "6") (pinfunction "PD1_OSC_OUT_6") (pintype "bidirectional"))
      (node (ref "Y1") (pin "1") (pinfunction "1_1") (pintype "passive"))
    )
    (net (code "76") (name "unconnected-(U2-NC-Pad4)") (class "Default")
      (node (ref "U2") (pin "4") (pinfunction "NC_4") (pintype "input"))
    )
    (net (code "77") (name "unconnected-(U3-PA5-Pad21)") (class "Default")
      (node (ref "U3") (pin "21") (pinfunction "PA5_21") (pintype "bidirectional"))
    )
    (net (code "78") (name "unconnected-(U3-PA8-Pad41)") (class "Default")
      (node (ref "U3") (pin "41") (pinfunction "PA8_41") (pintype "bidirectional"))
    )
    (net (code "79") (name "unconnected-(U3-PA15-Pad50)") (class "Default")
      (node (ref "U3") (pin "50") (pinfunction "PA15_50") (pintype "bidirectional"))
    )
    (net (code "80") (name "unconnected-(U3-PB3-Pad55)") (class "Default")
      (node (ref "U3") (pin "55") (pinfunction "PB3_55") (pintype "bidirectional"))
    )
    (net (code "81") (name "unconnected-(U3-PB4-Pad56)") (class "Default")
      (node (ref "U3") (pin "56") (pinfunction "PB4_56") (pintype "bidirectional"))
    )
    (net (code "82") (name "unconnected-(U3-PB5-Pad57)") (class "Default")
      (node (ref "U3") (pin "57") (pinfunction "PB5_57") (pintype "bidirectional"))
    )
    (net (code "83") (name "unconnected-(U3-PB6-Pad58)") (class "Default")
      (node (ref "U3") (pin "58") (pinfunction "PB6_58") (pintype "bidirectional"))
    )
    (net (code "84") (name "unconnected-(U3-PB7-Pad59)") (class "Default")
      (node (ref "U3") (pin "59") (pinfunction "PB7_59") (pintype "bidirectional"))
    )
    (net (code "85") (name "unconnected-(U3-PB8-Pad61)") (class "Default")
      (node (ref "U3") (pin "61") (pinfunction "PB8_61") (pintype "bidirectional"))
    )
    (net (code "86") (name "unconnected-(U3-PB9-Pad62)") (class "Default")
      (node (ref "U3") (pin "62") (pinfunction "PB9_62") (pintype "bidirectional"))
    )
    (net (code "87") (name "unconnected-(U3-PB15-Pad36)") (class "Default")
      (node (ref "U3") (pin "36") (pinfunction "PB15_36") (pintype "bidirectional"))
    )
    (net (code "88") (name "unconnected-(U3-PC3-Pad11)") (class "Default")
      (node (ref "U3") (pin "11") (pinfunction "PC3_11") (pintype "bidirectional"))
    )
    (net (code "89") (name "unconnected-(U3-PC6-Pad37)") (class "Default")
      (node (ref "U3") (pin "37") (pinfunction "PC6_37") (pintype "bidirectional"))
    )
    (net (code "90") (name "unconnected-(U3-PC7-Pad38)") (class "Default")
      (node (ref "U3") (pin "38") (pinfunction "PC7_38") (pintype "bidirectional"))
    )
    (net (code "91") (name "unconnected-(U3-PD2-Pad54)") (class "Default")
      (node (ref "U3") (pin "54") (pinfunction "PD2_54") (pintype "bidirectional"))
    )
    (net (code "92") (name "unconnected-(U3-VBAT-Pad1)") (class "Default")
      (node (ref "U3") (pin "1") (pinfunction "VBAT_1") (pintype "input"))
    )
  )
)
